# LoRaIOX_FW_RevA.net
KiCad netlist of a schematic drawn in EAGLE
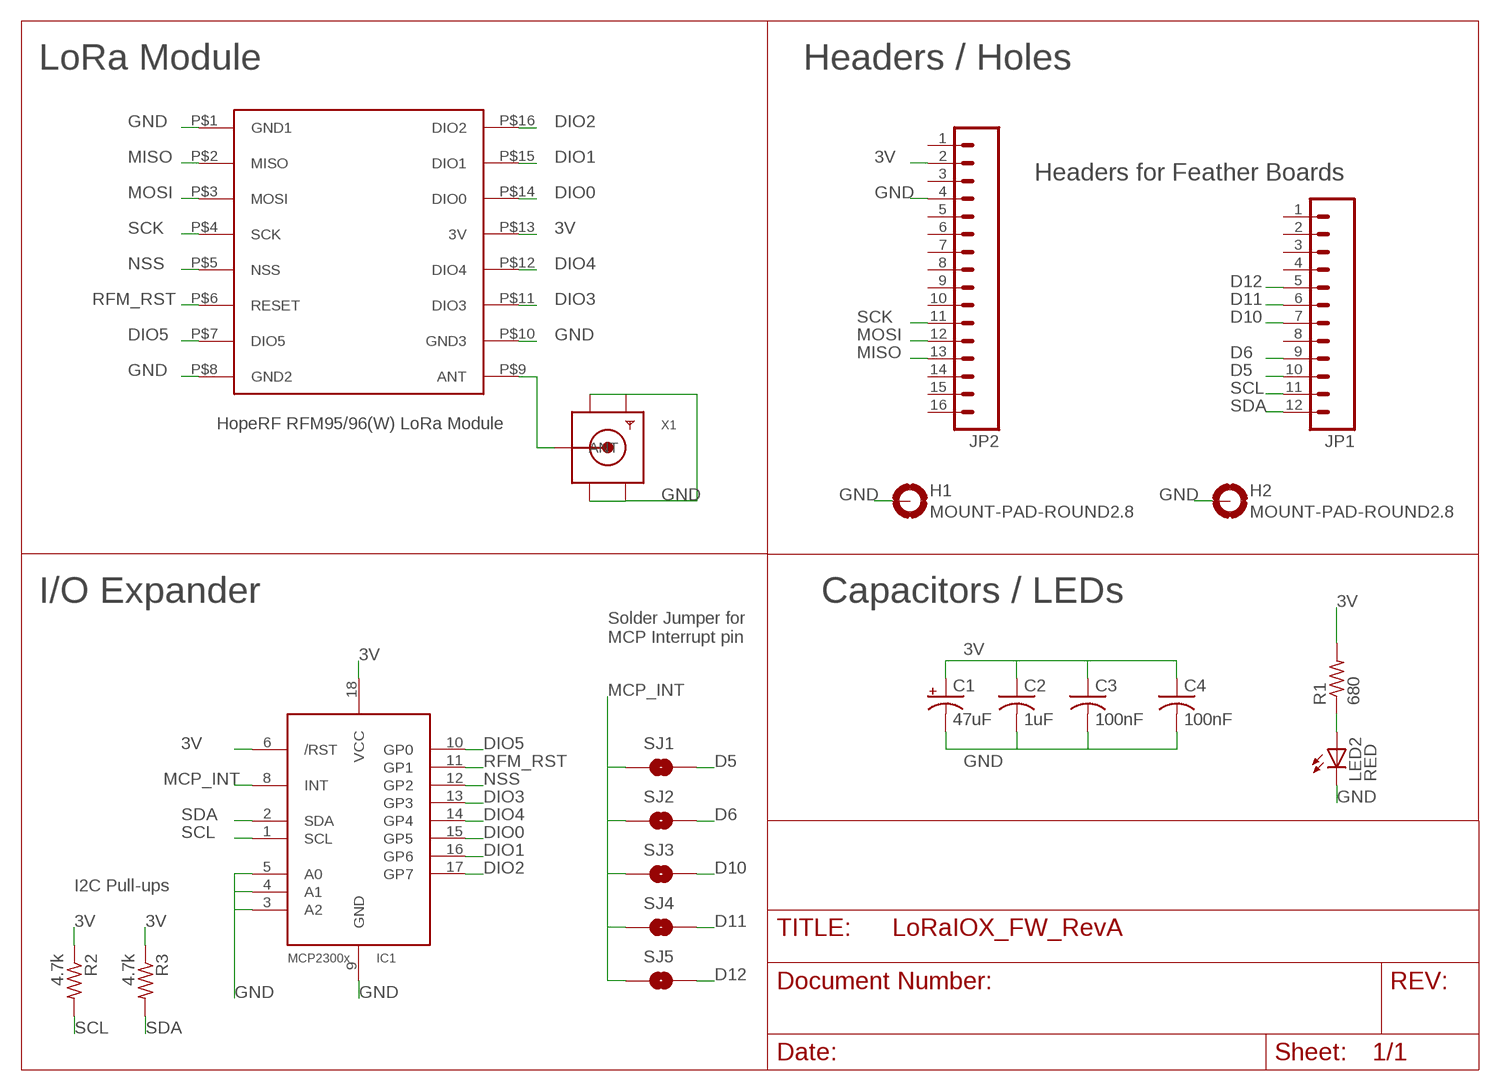
[diagram p0: schematic, sheet 1]

(export (version "E")
  (design (tool "Eeschema 10.0.6"))
  (components
    (comp (ref "C1")
      (value "47uF")
      (footprint "eagle-import:EIA3528")
      (libsource (lib "eagle-import") (part "47UF-10V-10%(TANT)"))
    )
    (comp (ref "C2")
      (value "1uF")
      (footprint "eagle-import:C0603")
      (libsource (lib "eagle-import") (part "C-USC0603"))
    )
    (comp (ref "C3")
      (value "100nF")
      (footprint "eagle-import:C0603")
      (libsource (lib "eagle-import") (part "C-USC0603"))
    )
    (comp (ref "C4")
      (value "100nF")
      (footprint "eagle-import:C0603")
      (libsource (lib "eagle-import") (part "C-USC0603"))
    )
    (comp (ref "H1")
      (value "MOUNT-PAD-ROUND2.8")
      (footprint "eagle-import:2,8-PAD")
      (libsource (lib "eagle-import") (part "MOUNT-PAD-ROUND2.8"))
    )
    (comp (ref "H2")
      (value "MOUNT-PAD-ROUND2.8")
      (footprint "eagle-import:2,8-PAD")
      (libsource (lib "eagle-import") (part "MOUNT-PAD-ROUND2.8"))
    )
    (comp (ref "IC1")
      (value "MCP2300X/SO")
      (footprint "eagle-import:SO18W")
      (libsource (lib "eagle-import") (part "MCP2300X/SO"))
    )
    (comp (ref "JP1")
      (value "M12NO_SILK")
      (footprint "eagle-import:1X12_NO_SILK")
      (libsource (lib "eagle-import") (part "M12NO_SILK"))
    )
    (comp (ref "JP2")
      (value "M161X16_NO_SILK")
      (footprint "eagle-import:1X16_NO_SILK")
      (libsource (lib "eagle-import") (part "M161X16_NO_SILK"))
    )
    (comp (ref "LED2")
      (value "RED")
      (footprint "eagle-import:CHIPLED_0805")
      (libsource (lib "eagle-import") (part "LEDCHIPLED_0805"))
    )
    (comp (ref "R1")
      (value "680")
      (footprint "eagle-import:R0603")
      (libsource (lib "eagle-import") (part "R-US_R0603"))
    )
    (comp (ref "R2")
      (value "4.7k")
      (footprint "eagle-import:R0603")
      (libsource (lib "eagle-import") (part "R-US_R0603"))
    )
    (comp (ref "R3")
      (value "4.7k")
      (footprint "eagle-import:R0603")
      (libsource (lib "eagle-import") (part "R-US_R0603"))
    )
    (comp (ref "SJ1")
      (value "JUMPER-PAD-2-NOYES_SILK")
      (footprint "eagle-import:PAD-JUMPER-2-NO_YES_SILK")
      (libsource (lib "eagle-import") (part "JUMPER-PAD-2-NOYES_SILK"))
    )
    (comp (ref "SJ2")
      (value "JUMPER-PAD-2-NOYES_SILK")
      (footprint "eagle-import:PAD-JUMPER-2-NO_YES_SILK")
      (libsource (lib "eagle-import") (part "JUMPER-PAD-2-NOYES_SILK"))
    )
    (comp (ref "SJ3")
      (value "JUMPER-PAD-2-NOYES_SILK")
      (footprint "eagle-import:PAD-JUMPER-2-NO_YES_SILK")
      (libsource (lib "eagle-import") (part "JUMPER-PAD-2-NOYES_SILK"))
    )
    (comp (ref "SJ4")
      (value "JUMPER-PAD-2-NOYES_SILK")
      (footprint "eagle-import:PAD-JUMPER-2-NO_YES_SILK")
      (libsource (lib "eagle-import") (part "JUMPER-PAD-2-NOYES_SILK"))
    )
    (comp (ref "SJ5")
      (value "JUMPER-PAD-2-NOYES_SILK")
      (footprint "eagle-import:PAD-JUMPER-2-NO_YES_SILK")
      (libsource (lib "eagle-import") (part "JUMPER-PAD-2-NOYES_SILK"))
    )
    (comp (ref "U$2")
      (value "RFM95W")
      (footprint "eagle-import:RFM95W")
      (libsource (lib "eagle-import") (part "RFM95W"))
    )
    (comp (ref "X1")
      (value "SMACONNECTOR_EDGE")
      (footprint "eagle-import:SMA_EDGELAUNCH")
      (libsource (lib "eagle-import") (part "SMACONNECTOR_EDGE"))
    )
  )
  (nets
    (net (code "1") (name "/3V") (class "Default")
      (node (ref "C1") (pin "A") (pinfunction "+_A") (pintype "passive"))
      (node (ref "C2") (pin "1") (pinfunction "1_1") (pintype "passive"))
      (node (ref "C3") (pin "1") (pinfunction "1_1") (pintype "passive"))
      (node (ref "C4") (pin "1") (pinfunction "1_1") (pintype "passive"))
      (node (ref "IC1") (pin "18") (pinfunction "VCC_18") (pintype "power_in"))
      (node (ref "IC1") (pin "6") (pinfunction "/RST_6") (pintype "input"))
      (node (ref "JP2") (pin "2") (pinfunction "2_2") (pintype "passive"))
      (node (ref "R1") (pin "2") (pinfunction "2_2") (pintype "passive"))
      (node (ref "R2") (pin "1") (pinfunction "1_1") (pintype "passive"))
      (node (ref "R3") (pin "1") (pinfunction "1_1") (pintype "passive"))
      (node (ref "U$2") (pin "P$13") (pinfunction "3V_P$13") (pintype "bidirectional"))
    )
    (net (code "2") (name "/D5") (class "Default")
      (node (ref "JP1") (pin "10") (pinfunction "10_10") (pintype "passive"))
      (node (ref "SJ1") (pin "2") (pinfunction "2_2") (pintype "passive"))
    )
    (net (code "3") (name "/D6") (class "Default")
      (node (ref "JP1") (pin "9") (pinfunction "9_9") (pintype "passive"))
      (node (ref "SJ2") (pin "2") (pinfunction "2_2") (pintype "passive"))
    )
    (net (code "4") (name "/D10") (class "Default")
      (node (ref "JP1") (pin "7") (pinfunction "7_7") (pintype "passive"))
      (node (ref "SJ3") (pin "2") (pinfunction "2_2") (pintype "passive"))
    )
    (net (code "5") (name "/D11") (class "Default")
      (node (ref "JP1") (pin "6") (pinfunction "6_6") (pintype "passive"))
      (node (ref "SJ4") (pin "2") (pinfunction "2_2") (pintype "passive"))
    )
    (net (code "6") (name "/D12") (class "Default")
      (node (ref "JP1") (pin "5") (pinfunction "5_5") (pintype "passive"))
      (node (ref "SJ5") (pin "2") (pinfunction "2_2") (pintype "passive"))
    )
    (net (code "7") (name "/DIO0") (class "Default")
      (node (ref "IC1") (pin "15") (pinfunction "GP5_15") (pintype "bidirectional"))
      (node (ref "U$2") (pin "P$14") (pinfunction "DIO0_P$14") (pintype "bidirectional"))
    )
    (net (code "8") (name "/DIO1") (class "Default")
      (node (ref "IC1") (pin "16") (pinfunction "GP6_16") (pintype "bidirectional"))
      (node (ref "U$2") (pin "P$15") (pinfunction "DIO1_P$15") (pintype "bidirectional"))
    )
    (net (code "9") (name "/DIO2") (class "Default")
      (node (ref "IC1") (pin "17") (pinfunction "GP7_17") (pintype "bidirectional"))
      (node (ref "U$2") (pin "P$16") (pinfunction "DIO2_P$16") (pintype "bidirectional"))
    )
    (net (code "10") (name "/DIO3") (class "Default")
      (node (ref "IC1") (pin "13") (pinfunction "GP3_13") (pintype "bidirectional"))
      (node (ref "U$2") (pin "P$11") (pinfunction "DIO3_P$11") (pintype "bidirectional"))
    )
    (net (code "11") (name "/DIO4") (class "Default")
      (node (ref "IC1") (pin "14") (pinfunction "GP4_14") (pintype "bidirectional"))
      (node (ref "U$2") (pin "P$12") (pinfunction "DIO4_P$12") (pintype "bidirectional"))
    )
    (net (code "12") (name "/DIO5") (class "Default")
      (node (ref "IC1") (pin "10") (pinfunction "GP0_10") (pintype "bidirectional"))
      (node (ref "U$2") (pin "P$7") (pinfunction "DIO5_P$7") (pintype "bidirectional"))
    )
    (net (code "13") (name "/GND") (class "Default")
      (node (ref "C1") (pin "C") (pinfunction "-_C") (pintype "passive"))
      (node (ref "C2") (pin "2") (pinfunction "2_2") (pintype "passive"))
      (node (ref "C3") (pin "2") (pinfunction "2_2") (pintype "passive"))
      (node (ref "C4") (pin "2") (pinfunction "2_2") (pintype "passive"))
      (node (ref "H1") (pin "B2,8") (pinfunction "MOUNT_B2,8") (pintype "passive"))
      (node (ref "H2") (pin "B2,8") (pinfunction "MOUNT_B2,8") (pintype "passive"))
      (node (ref "IC1") (pin "3") (pinfunction "A2_3") (pintype "input"))
      (node (ref "IC1") (pin "4") (pinfunction "A1_4") (pintype "input"))
      (node (ref "IC1") (pin "5") (pinfunction "A0_5") (pintype "input"))
      (node (ref "IC1") (pin "9") (pinfunction "GND_9") (pintype "power_in"))
      (node (ref "JP2") (pin "4") (pinfunction "4_4") (pintype "passive"))
      (node (ref "LED2") (pin "C") (pinfunction "C_C") (pintype "passive"))
      (node (ref "U$2") (pin "P$1") (pinfunction "GND1_P$1") (pintype "bidirectional"))
      (node (ref "U$2") (pin "P$10") (pinfunction "GND3_P$10") (pintype "bidirectional"))
      (node (ref "U$2") (pin "P$8") (pinfunction "GND2_P$8") (pintype "bidirectional"))
      (node (ref "X1") (pin "GND@1") (pinfunction "GND4_GND@1") (pintype "power_in"))
      (node (ref "X1") (pin "GND@2") (pinfunction "GND3_GND@2") (pintype "power_in"))
      (node (ref "X1") (pin "GND@3") (pinfunction "GND2_GND@3") (pintype "power_in"))
      (node (ref "X1") (pin "GND@4") (pinfunction "GND1_GND@4") (pintype "power_in"))
    )
    (net (code "14") (name "/MCP_INT") (class "Default")
      (node (ref "IC1") (pin "8") (pinfunction "INT_8") (pintype "output"))
      (node (ref "SJ1") (pin "1") (pinfunction "1_1") (pintype "passive"))
      (node (ref "SJ2") (pin "1") (pinfunction "1_1") (pintype "passive"))
      (node (ref "SJ3") (pin "1") (pinfunction "1_1") (pintype "passive"))
      (node (ref "SJ4") (pin "1") (pinfunction "1_1") (pintype "passive"))
      (node (ref "SJ5") (pin "1") (pinfunction "1_1") (pintype "passive"))
    )
    (net (code "15") (name "/MISO") (class "Default")
      (node (ref "JP2") (pin "13") (pinfunction "13_13") (pintype "passive"))
      (node (ref "U$2") (pin "P$2") (pinfunction "MISO_P$2") (pintype "bidirectional"))
    )
    (net (code "16") (name "/MOSI") (class "Default")
      (node (ref "JP2") (pin "12") (pinfunction "12_12") (pintype "passive"))
      (node (ref "U$2") (pin "P$3") (pinfunction "MOSI_P$3") (pintype "bidirectional"))
    )
    (net (code "17") (name "/NSS") (class "Default")
      (node (ref "IC1") (pin "12") (pinfunction "GP2_12") (pintype "bidirectional"))
      (node (ref "U$2") (pin "P$5") (pinfunction "NSS_P$5") (pintype "bidirectional"))
    )
    (net (code "18") (name "/RFM_RST") (class "Default")
      (node (ref "IC1") (pin "11") (pinfunction "GP1_11") (pintype "bidirectional"))
      (node (ref "U$2") (pin "P$6") (pinfunction "RESET_P$6") (pintype "bidirectional"))
    )
    (net (code "19") (name "/SCK") (class "Default")
      (node (ref "JP2") (pin "11") (pinfunction "11_11") (pintype "passive"))
      (node (ref "U$2") (pin "P$4") (pinfunction "SCK_P$4") (pintype "bidirectional"))
    )
    (net (code "20") (name "/SCL") (class "Default")
      (node (ref "IC1") (pin "1") (pinfunction "SCL_1") (pintype "bidirectional"))
      (node (ref "JP1") (pin "11") (pinfunction "11_11") (pintype "passive"))
      (node (ref "R2") (pin "2") (pinfunction "2_2") (pintype "passive"))
    )
    (net (code "21") (name "/SDA") (class "Default")
      (node (ref "IC1") (pin "2") (pinfunction "SDA_2") (pintype "bidirectional"))
      (node (ref "JP1") (pin "12") (pinfunction "12_12") (pintype "passive"))
      (node (ref "R3") (pin "2") (pinfunction "2_2") (pintype "passive"))
    )
    (net (code "22") (name "Net-(LED2-PadA)") (class "Default")
      (node (ref "LED2") (pin "A") (pinfunction "A_A") (pintype "passive"))
      (node (ref "R1") (pin "1") (pinfunction "1_1") (pintype "passive"))
    )
    (net (code "23") (name "Net-(U$2-ANT)") (class "Default")
      (node (ref "U$2") (pin "P$9") (pinfunction "ANT_P$9") (pintype "bidirectional"))
      (node (ref "X1") (pin "P") (pinfunction "ANT_P") (pintype "bidirectional"))
    )
    (net (code "24") (name "unconnected-(JP1-Pad1)") (class "Default")
      (node (ref "JP1") (pin "1") (pinfunction "1_1") (pintype "passive"))
    )
    (net (code "25") (name "unconnected-(JP1-Pad2)") (class "Default")
      (node (ref "JP1") (pin "2") (pinfunction "2_2") (pintype "passive"))
    )
    (net (code "26") (name "unconnected-(JP1-Pad3)") (class "Default")
      (node (ref "JP1") (pin "3") (pinfunction "3_3") (pintype "passive"))
    )
    (net (code "27") (name "unconnected-(JP1-Pad4)") (class "Default")
      (node (ref "JP1") (pin "4") (pinfunction "4_4") (pintype "passive"))
    )
    (net (code "28") (name "unconnected-(JP1-Pad8)") (class "Default")
      (node (ref "JP1") (pin "8") (pinfunction "8_8") (pintype "passive"))
    )
    (net (code "29") (name "unconnected-(JP2-Pad1)") (class "Default")
      (node (ref "JP2") (pin "1") (pinfunction "1_1") (pintype "passive"))
    )
    (net (code "30") (name "unconnected-(JP2-Pad3)") (class "Default")
      (node (ref "JP2") (pin "3") (pinfunction "3_3") (pintype "passive"))
    )
    (net (code "31") (name "unconnected-(JP2-Pad5)") (class "Default")
      (node (ref "JP2") (pin "5") (pinfunction "5_5") (pintype "passive"))
    )
    (net (code "32") (name "unconnected-(JP2-Pad6)") (class "Default")
      (node (ref "JP2") (pin "6") (pinfunction "6_6") (pintype "passive"))
    )
    (net (code "33") (name "unconnected-(JP2-Pad7)") (class "Default")
      (node (ref "JP2") (pin "7") (pinfunction "7_7") (pintype "passive"))
    )
    (net (code "34") (name "unconnected-(JP2-Pad8)") (class "Default")
      (node (ref "JP2") (pin "8") (pinfunction "8_8") (pintype "passive"))
    )
    (net (code "35") (name "unconnected-(JP2-Pad9)") (class "Default")
      (node (ref "JP2") (pin "9") (pinfunction "9_9") (pintype "passive"))
    )
    (net (code "36") (name "unconnected-(JP2-Pad10)") (class "Default")
      (node (ref "JP2") (pin "10") (pinfunction "10_10") (pintype "passive"))
    )
    (net (code "37") (name "unconnected-(JP2-Pad14)") (class "Default")
      (node (ref "JP2") (pin "14") (pinfunction "14_14") (pintype "passive"))
    )
    (net (code "38") (name "unconnected-(JP2-Pad15)") (class "Default")
      (node (ref "JP2") (pin "15") (pinfunction "15_15") (pintype "passive"))
    )
    (net (code "39") (name "unconnected-(JP2-Pad16)") (class "Default")
      (node (ref "JP2") (pin "16") (pinfunction "16_16") (pintype "passive"))
    )
  )
)
